# C3427-3.net
KiCad netlist of a schematic drawn in EAGLE
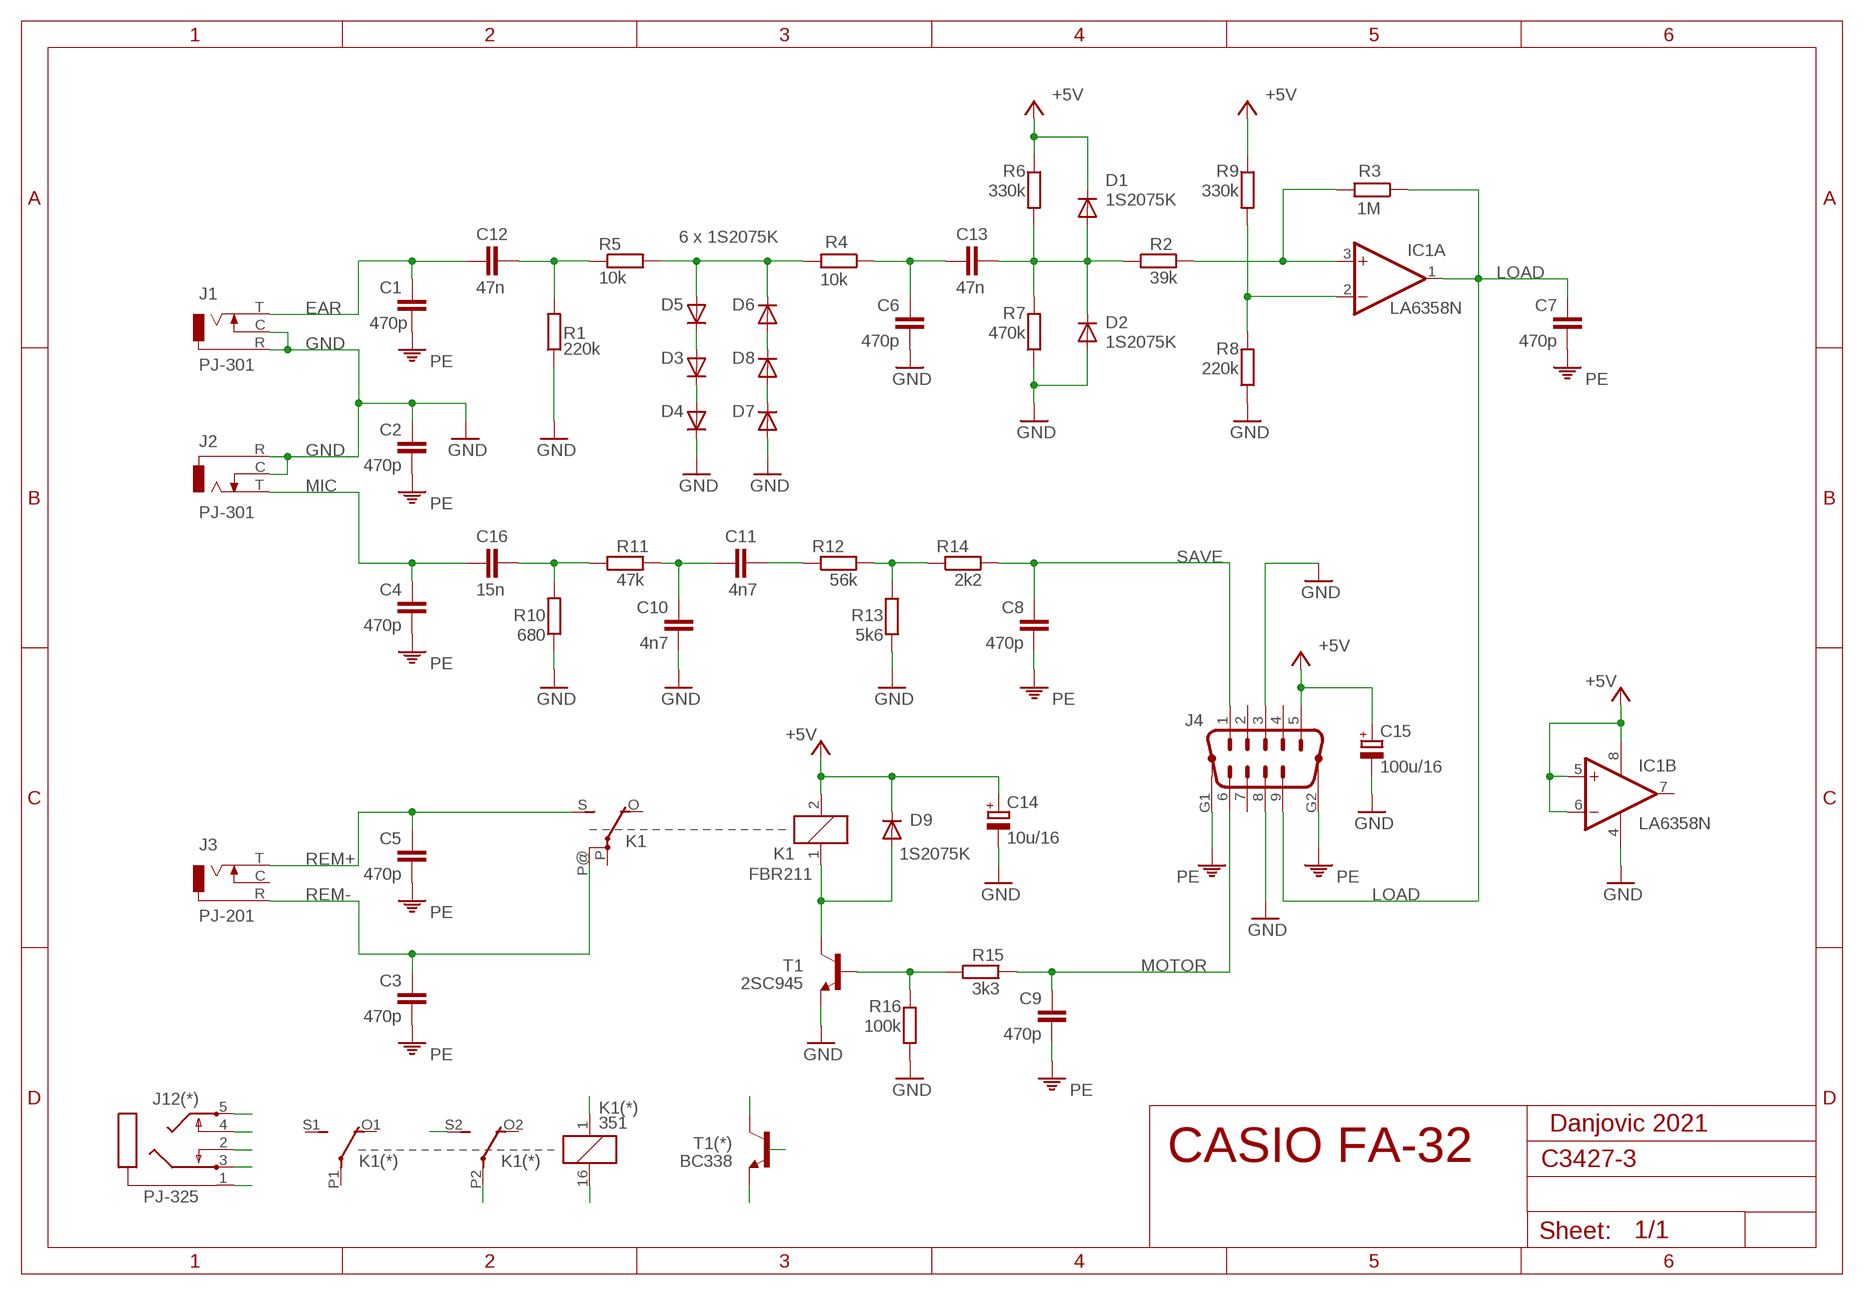
[diagram p0: schematic, sheet 1]

(export (version "E")
  (design (tool "Eeschema 10.0.6"))
  (components
    (comp (ref "C1")
      (value "470p")
      (footprint "eagle-import:C050-024X044")
      (libsource (lib "eagle-import") (part "C-EU050-024X044"))
    )
    (comp (ref "C2")
      (value "470p")
      (footprint "eagle-import:C050-024X044")
      (libsource (lib "eagle-import") (part "C-EU050-024X044"))
    )
    (comp (ref "C3")
      (value "470p")
      (footprint "eagle-import:C050-024X044")
      (libsource (lib "eagle-import") (part "C-EU050-024X044"))
    )
    (comp (ref "C4")
      (value "470p")
      (footprint "eagle-import:C050-024X044")
      (libsource (lib "eagle-import") (part "C-EU050-024X044"))
    )
    (comp (ref "C5")
      (value "470p")
      (footprint "eagle-import:C050-024X044")
      (libsource (lib "eagle-import") (part "C-EU050-024X044"))
    )
    (comp (ref "C6")
      (value "470p")
      (footprint "eagle-import:C050-024X044")
      (libsource (lib "eagle-import") (part "C-EU050-024X044"))
    )
    (comp (ref "C7")
      (value "470p")
      (footprint "eagle-import:C050-024X044")
      (libsource (lib "eagle-import") (part "C-EU050-024X044"))
    )
    (comp (ref "C8")
      (value "470p")
      (footprint "eagle-import:C050-024X044")
      (libsource (lib "eagle-import") (part "C-EU050-024X044"))
    )
    (comp (ref "C9")
      (value "470p")
      (footprint "eagle-import:C050-024X044")
      (libsource (lib "eagle-import") (part "C-EU050-024X044"))
    )
    (comp (ref "C10")
      (value "4n7")
      (footprint "eagle-import:C050-024X044")
      (libsource (lib "eagle-import") (part "C-EU050-024X044"))
    )
    (comp (ref "C11")
      (value "4n7")
      (footprint "eagle-import:C050-024X044")
      (libsource (lib "eagle-import") (part "C-EU050-024X044"))
    )
    (comp (ref "C12")
      (value "47n")
      (footprint "eagle-import:C050-045X075")
      (libsource (lib "eagle-import") (part "C-EU050-045X075"))
    )
    (comp (ref "C13")
      (value "47n")
      (footprint "eagle-import:C050-045X075")
      (libsource (lib "eagle-import") (part "C-EU050-045X075"))
    )
    (comp (ref "C14")
      (value "10u/16")
      (footprint "eagle-import:E2-4")
      (libsource (lib "eagle-import") (part "CPOL-EUE2-4"))
    )
    (comp (ref "C15")
      (value "100u/16")
      (footprint "eagle-import:E2,5-6")
      (libsource (lib "eagle-import") (part "CPOL-EUE2.5-6"))
    )
    (comp (ref "C16")
      (value "15n")
      (footprint "eagle-import:C050-024X044")
      (libsource (lib "eagle-import") (part "C-EU050-024X044"))
    )
    (comp (ref "D1")
      (value "1S2075K")
      (footprint "eagle-import:D-7.5")
      (libsource (lib "eagle-import") (part "DIODE-D-7.5"))
    )
    (comp (ref "D2")
      (value "1S2075K")
      (footprint "eagle-import:D-7.5")
      (libsource (lib "eagle-import") (part "DIODE-D-7.5"))
    )
    (comp (ref "D3")
      (value "1S2075K")
      (footprint "eagle-import:D-7.5")
      (libsource (lib "eagle-import") (part "DIODE-D-7.5"))
    )
    (comp (ref "D4")
      (value "1S2075K")
      (footprint "eagle-import:D-7.5")
      (libsource (lib "eagle-import") (part "DIODE-D-7.5"))
    )
    (comp (ref "D5")
      (value "1S2075K")
      (footprint "eagle-import:D-7.5")
      (libsource (lib "eagle-import") (part "DIODE-D-7.5"))
    )
    (comp (ref "D6")
      (value "1S2075K")
      (footprint "eagle-import:D-7.5")
      (libsource (lib "eagle-import") (part "DIODE-D-7.5"))
    )
    (comp (ref "D7")
      (value "1S2075K")
      (footprint "eagle-import:D-7.5")
      (libsource (lib "eagle-import") (part "DIODE-D-7.5"))
    )
    (comp (ref "D8")
      (value "1S2075K")
      (footprint "eagle-import:D-7.5")
      (libsource (lib "eagle-import") (part "DIODE-D-7.5"))
    )
    (comp (ref "D9")
      (value "1S2075K")
      (footprint "eagle-import:D-7.5")
      (libsource (lib "eagle-import") (part "DIODE-D-7.5"))
    )
    (comp (ref "IC1")
      (value "LA6358N")
      (footprint "eagle-import:DIL08")
      (libsource (lib "eagle-import") (part "LM358N"))
    )
    (comp (ref "J1")
      (value "PJ-301")
      (footprint "eagle-import:PJ301")
      (libsource (lib "eagle-import") (part "PJ-301"))
    )
    (comp (ref "J2")
      (value "PJ-301")
      (footprint "eagle-import:PJ301")
      (libsource (lib "eagle-import") (part "PJ-301"))
    )
    (comp (ref "J3")
      (value "PJ-201")
      (footprint "eagle-import:PJ201")
      (libsource (lib "eagle-import") (part "PJ-201"))
    )
    (comp (ref "J4")
      (value "M09HP")
      (footprint "eagle-import:M09HP")
      (libsource (lib "eagle-import") (part "M09HP"))
    )
    (comp (ref "J12(*)")
      (value "PJ-325")
      (footprint "eagle-import:PJ325")
      (libsource (lib "eagle-import") (part "PJ-325"))
    )
    (comp (ref "K1")
      (value "FBR211")
      (footprint "eagle-import:FRS1B")
      (libsource (lib "eagle-import") (part "FRS1B"))
    )
    (comp (ref "K1(*)")
      (value "351")
      (footprint "eagle-import:351")
      (libsource (lib "eagle-import") (part "351"))
    )
    (comp (ref "R1")
      (value "220k")
      (footprint "eagle-import:0204_7")
      (libsource (lib "eagle-import") (part "R-EU_0204/7"))
    )
    (comp (ref "R2")
      (value "39k")
      (footprint "eagle-import:0204_7")
      (libsource (lib "eagle-import") (part "R-EU_0204/7"))
    )
    (comp (ref "R3")
      (value "1M")
      (footprint "eagle-import:0204_7")
      (libsource (lib "eagle-import") (part "R-EU_0204/7"))
    )
    (comp (ref "R4")
      (value "10k")
      (footprint "eagle-import:0204_7")
      (libsource (lib "eagle-import") (part "R-EU_0204/7"))
    )
    (comp (ref "R5")
      (value "10k")
      (footprint "eagle-import:0204_7")
      (libsource (lib "eagle-import") (part "R-EU_0204/7"))
    )
    (comp (ref "R6")
      (value "330k")
      (footprint "eagle-import:0204_7")
      (libsource (lib "eagle-import") (part "R-EU_0204/7"))
    )
    (comp (ref "R7")
      (value "470k")
      (footprint "eagle-import:0204_7")
      (libsource (lib "eagle-import") (part "R-EU_0204/7"))
    )
    (comp (ref "R8")
      (value "220k")
      (footprint "eagle-import:0204_7")
      (libsource (lib "eagle-import") (part "R-EU_0204/7"))
    )
    (comp (ref "R9")
      (value "330k")
      (footprint "eagle-import:0204_7")
      (libsource (lib "eagle-import") (part "R-EU_0204/7"))
    )
    (comp (ref "R10")
      (value "680")
      (footprint "eagle-import:0204_7")
      (libsource (lib "eagle-import") (part "R-EU_0204/7"))
    )
    (comp (ref "R11")
      (value "47k")
      (footprint "eagle-import:0204_7")
      (libsource (lib "eagle-import") (part "R-EU_0204/7"))
    )
    (comp (ref "R12")
      (value "56k")
      (footprint "eagle-import:0204_7")
      (libsource (lib "eagle-import") (part "R-EU_0204/7"))
    )
    (comp (ref "R13")
      (value "5k6")
      (footprint "eagle-import:0204_7")
      (libsource (lib "eagle-import") (part "R-EU_0204/7"))
    )
    (comp (ref "R14")
      (value "2k2")
      (footprint "eagle-import:0204_7")
      (libsource (lib "eagle-import") (part "R-EU_0204/7"))
    )
    (comp (ref "R15")
      (value "3k3")
      (footprint "eagle-import:0204_7")
      (libsource (lib "eagle-import") (part "R-EU_0204/7"))
    )
    (comp (ref "R16")
      (value "100k")
      (footprint "eagle-import:0204_7")
      (libsource (lib "eagle-import") (part "R-EU_0204/7"))
    )
    (comp (ref "T1")
      (value "2SC945")
      (footprint "eagle-import:TO92-ECB")
      (libsource (lib "eagle-import") (part "2SC945"))
    )
    (comp (ref "T1(*)")
      (value "BC338")
      (footprint "eagle-import:TO92-EBC")
      (libsource (lib "eagle-import") (part "BC338"))
    )
  )
  (nets
    (net (code "1") (name "+5V") (class "Default")
      (node (ref "C14") (pin "+") (pinfunction "+_+") (pintype "passive"))
      (node (ref "C15") (pin "+") (pinfunction "+_+") (pintype "passive"))
      (node (ref "D1") (pin "C") (pinfunction "C_C") (pintype "passive"))
      (node (ref "D9") (pin "C") (pinfunction "C_C") (pintype "passive"))
      (node (ref "IC1") (pin "5") (pinfunction "+IN_5") (pintype "input"))
      (node (ref "IC1") (pin "6") (pinfunction "-IN_6") (pintype "input"))
      (node (ref "IC1") (pin "8") (pinfunction "V+_8") (pintype "power_in"))
      (node (ref "J4") (pin "5") (pinfunction "5_5") (pintype "passive"))
      (node (ref "K1") (pin "2") (pinfunction "2_2") (pintype "passive"))
      (node (ref "K1(*)") (pin "1") (pinfunction "1_1") (pintype "passive"))
      (node (ref "R6") (pin "1") (pinfunction "1_1") (pintype "passive"))
      (node (ref "R9") (pin "1") (pinfunction "1_1") (pintype "passive"))
    )
    (net (code "2") (name "/EAR") (class "Default")
      (node (ref "C1") (pin "2") (pinfunction "2_2") (pintype "passive"))
      (node (ref "C12") (pin "2") (pinfunction "2_2") (pintype "passive"))
      (node (ref "J1") (pin "T") (pinfunction "T_T") (pintype "passive"))
      (node (ref "J12(*)") (pin "5") (pinfunction "5_5") (pintype "passive"))
    )
    (net (code "3") (name "/LOAD") (class "Default")
      (node (ref "C7") (pin "2") (pinfunction "2_2") (pintype "passive"))
      (node (ref "IC1") (pin "1") (pinfunction "OUT_1") (pintype "output"))
      (node (ref "J4") (pin "9") (pinfunction "9_9") (pintype "passive"))
      (node (ref "R3") (pin "1") (pinfunction "1_1") (pintype "passive"))
    )
    (net (code "4") (name "/MIC") (class "Default")
      (node (ref "C16") (pin "2") (pinfunction "2_2") (pintype "passive"))
      (node (ref "C4") (pin "2") (pinfunction "2_2") (pintype "passive"))
      (node (ref "J12(*)") (pin "3") (pinfunction "3_3") (pintype "passive"))
      (node (ref "J2") (pin "T") (pinfunction "T_T") (pintype "passive"))
    )
    (net (code "5") (name "/MOTOR") (class "Default")
      (node (ref "C9") (pin "2") (pinfunction "2_2") (pintype "passive"))
      (node (ref "J4") (pin "6") (pinfunction "6_6") (pintype "passive"))
      (node (ref "R15") (pin "2") (pinfunction "2_2") (pintype "passive"))
    )
    (net (code "6") (name "/N$9") (class "Default")
      (node (ref "D9") (pin "A") (pinfunction "A_A") (pintype "passive"))
      (node (ref "K1") (pin "1") (pinfunction "1_1") (pintype "passive"))
      (node (ref "K1(*)") (pin "16") (pinfunction "2_16") (pintype "passive"))
      (node (ref "T1") (pin "C") (pinfunction "C_C") (pintype "passive"))
      (node (ref "T1(*)") (pin "C") (pinfunction "C_C") (pintype "passive"))
    )
    (net (code "7") (name "/N$10") (class "Default")
      (node (ref "R15") (pin "1") (pinfunction "1_1") (pintype "passive"))
      (node (ref "R16") (pin "1") (pinfunction "1_1") (pintype "passive"))
      (node (ref "T1") (pin "B") (pinfunction "B_B") (pintype "passive"))
      (node (ref "T1(*)") (pin "B") (pinfunction "B_B") (pintype "passive"))
    )
    (net (code "8") (name "/REM+") (class "Default")
      (node (ref "C5") (pin "2") (pinfunction "2_2") (pintype "passive"))
      (node (ref "J3") (pin "T") (pinfunction "T_T") (pintype "passive"))
      (node (ref "K1") (pin "S") (pinfunction "S_S") (pintype "passive"))
      (node (ref "K1(*)") (pin "P2") (pinfunction "P_P2") (pintype "passive"))
    )
    (net (code "9") (name "/REM-") (class "Default")
      (node (ref "C3") (pin "2") (pinfunction "2_2") (pintype "passive"))
      (node (ref "J3") (pin "R") (pinfunction "R_R") (pintype "passive"))
      (node (ref "K1") (pin "P@") (pinfunction "P_P@") (pintype "passive"))
      (node (ref "K1(*)") (pin "S2") (pinfunction "S_S2") (pintype "passive"))
    )
    (net (code "10") (name "/SAVE") (class "Default")
      (node (ref "C8") (pin "2") (pinfunction "2_2") (pintype "passive"))
      (node (ref "J4") (pin "1") (pinfunction "1_1") (pintype "passive"))
      (node (ref "R14") (pin "2") (pinfunction "2_2") (pintype "passive"))
    )
    (net (code "11") (name "GND") (class "Default")
      (node (ref "C10") (pin "1") (pinfunction "1_1") (pintype "passive"))
      (node (ref "C14") (pin "-") (pinfunction "-_-") (pintype "passive"))
      (node (ref "C15") (pin "-") (pinfunction "-_-") (pintype "passive"))
      (node (ref "C2") (pin "2") (pinfunction "2_2") (pintype "passive"))
      (node (ref "C6") (pin "1") (pinfunction "1_1") (pintype "passive"))
      (node (ref "D2") (pin "A") (pinfunction "A_A") (pintype "passive"))
      (node (ref "D4") (pin "C") (pinfunction "C_C") (pintype "passive"))
      (node (ref "D7") (pin "A") (pinfunction "A_A") (pintype "passive"))
      (node (ref "IC1") (pin "4") (pinfunction "V-_4") (pintype "power_in"))
      (node (ref "J1") (pin "C") (pinfunction "C_C") (pintype "passive"))
      (node (ref "J1") (pin "R") (pinfunction "R_R") (pintype "passive"))
      (node (ref "J12(*)") (pin "1") (pinfunction "1_1") (pintype "passive"))
      (node (ref "J12(*)") (pin "2") (pinfunction "2_2") (pintype "passive"))
      (node (ref "J12(*)") (pin "4") (pinfunction "4_4") (pintype "passive"))
      (node (ref "J2") (pin "C") (pinfunction "C_C") (pintype "passive"))
      (node (ref "J2") (pin "R") (pinfunction "R_R") (pintype "passive"))
      (node (ref "J4") (pin "3") (pinfunction "3_3") (pintype "passive"))
      (node (ref "J4") (pin "8") (pinfunction "8_8") (pintype "passive"))
      (node (ref "R1") (pin "1") (pinfunction "1_1") (pintype "passive"))
      (node (ref "R10") (pin "1") (pinfunction "1_1") (pintype "passive"))
      (node (ref "R13") (pin "2") (pinfunction "2_2") (pintype "passive"))
      (node (ref "R16") (pin "2") (pinfunction "2_2") (pintype "passive"))
      (node (ref "R7") (pin "1") (pinfunction "1_1") (pintype "passive"))
      (node (ref "R8") (pin "1") (pinfunction "1_1") (pintype "passive"))
      (node (ref "T1") (pin "E") (pinfunction "E_E") (pintype "passive"))
      (node (ref "T1(*)") (pin "E") (pinfunction "E_E") (pintype "passive"))
    )
    (net (code "12") (name "Net-(C10-Pad2)") (class "Default")
      (node (ref "C10") (pin "2") (pinfunction "2_2") (pintype "passive"))
      (node (ref "C11") (pin "1") (pinfunction "1_1") (pintype "passive"))
      (node (ref "R11") (pin "2") (pinfunction "2_2") (pintype "passive"))
    )
    (net (code "13") (name "Net-(C11-Pad2)") (class "Default")
      (node (ref "C11") (pin "2") (pinfunction "2_2") (pintype "passive"))
      (node (ref "R12") (pin "1") (pinfunction "1_1") (pintype "passive"))
    )
    (net (code "14") (name "Net-(C12-Pad1)") (class "Default")
      (node (ref "C12") (pin "1") (pinfunction "1_1") (pintype "passive"))
      (node (ref "R1") (pin "2") (pinfunction "2_2") (pintype "passive"))
      (node (ref "R5") (pin "1") (pinfunction "1_1") (pintype "passive"))
    )
    (net (code "15") (name "Net-(C13-Pad1)") (class "Default")
      (node (ref "C13") (pin "1") (pinfunction "1_1") (pintype "passive"))
      (node (ref "D1") (pin "A") (pinfunction "A_A") (pintype "passive"))
      (node (ref "D2") (pin "C") (pinfunction "C_C") (pintype "passive"))
      (node (ref "R2") (pin "1") (pinfunction "1_1") (pintype "passive"))
      (node (ref "R6") (pin "2") (pinfunction "2_2") (pintype "passive"))
      (node (ref "R7") (pin "2") (pinfunction "2_2") (pintype "passive"))
    )
    (net (code "16") (name "Net-(C13-Pad2)") (class "Default")
      (node (ref "C13") (pin "2") (pinfunction "2_2") (pintype "passive"))
      (node (ref "C6") (pin "2") (pinfunction "2_2") (pintype "passive"))
      (node (ref "R4") (pin "1") (pinfunction "1_1") (pintype "passive"))
    )
    (net (code "17") (name "Net-(C16-Pad1)") (class "Default")
      (node (ref "C16") (pin "1") (pinfunction "1_1") (pintype "passive"))
      (node (ref "R10") (pin "2") (pinfunction "2_2") (pintype "passive"))
      (node (ref "R11") (pin "1") (pinfunction "1_1") (pintype "passive"))
    )
    (net (code "18") (name "Net-(D3-PadA)") (class "Default")
      (node (ref "D3") (pin "A") (pinfunction "A_A") (pintype "passive"))
      (node (ref "D5") (pin "C") (pinfunction "C_C") (pintype "passive"))
    )
    (net (code "19") (name "Net-(D3-PadC)") (class "Default")
      (node (ref "D3") (pin "C") (pinfunction "C_C") (pintype "passive"))
      (node (ref "D4") (pin "A") (pinfunction "A_A") (pintype "passive"))
    )
    (net (code "20") (name "Net-(D5-PadA)") (class "Default")
      (node (ref "D5") (pin "A") (pinfunction "A_A") (pintype "passive"))
      (node (ref "D6") (pin "C") (pinfunction "C_C") (pintype "passive"))
      (node (ref "R4") (pin "2") (pinfunction "2_2") (pintype "passive"))
      (node (ref "R5") (pin "2") (pinfunction "2_2") (pintype "passive"))
    )
    (net (code "21") (name "Net-(D6-PadA)") (class "Default")
      (node (ref "D6") (pin "A") (pinfunction "A_A") (pintype "passive"))
      (node (ref "D8") (pin "C") (pinfunction "C_C") (pintype "passive"))
    )
    (net (code "22") (name "Net-(D7-PadC)") (class "Default")
      (node (ref "D7") (pin "C") (pinfunction "C_C") (pintype "passive"))
      (node (ref "D8") (pin "A") (pinfunction "A_A") (pintype "passive"))
    )
    (net (code "23") (name "Net-(IC1A-+IN)") (class "Default")
      (node (ref "IC1") (pin "3") (pinfunction "+IN_3") (pintype "input"))
      (node (ref "R2") (pin "2") (pinfunction "2_2") (pintype "passive"))
      (node (ref "R3") (pin "2") (pinfunction "2_2") (pintype "passive"))
    )
    (net (code "24") (name "Net-(IC1A--IN)") (class "Default")
      (node (ref "IC1") (pin "2") (pinfunction "-IN_2") (pintype "input"))
      (node (ref "R8") (pin "2") (pinfunction "2_2") (pintype "passive"))
      (node (ref "R9") (pin "2") (pinfunction "2_2") (pintype "passive"))
    )
    (net (code "25") (name "Net-(R12-Pad2)") (class "Default")
      (node (ref "R12") (pin "2") (pinfunction "2_2") (pintype "passive"))
      (node (ref "R13") (pin "1") (pinfunction "1_1") (pintype "passive"))
      (node (ref "R14") (pin "1") (pinfunction "1_1") (pintype "passive"))
    )
    (net (code "26") (name "PE") (class "Default")
      (node (ref "C1") (pin "1") (pinfunction "1_1") (pintype "passive"))
      (node (ref "C2") (pin "1") (pinfunction "1_1") (pintype "passive"))
      (node (ref "C3") (pin "1") (pinfunction "1_1") (pintype "passive"))
      (node (ref "C4") (pin "1") (pinfunction "1_1") (pintype "passive"))
      (node (ref "C5") (pin "1") (pinfunction "1_1") (pintype "passive"))
      (node (ref "C7") (pin "1") (pinfunction "1_1") (pintype "passive"))
      (node (ref "C8") (pin "1") (pinfunction "1_1") (pintype "passive"))
      (node (ref "C9") (pin "1") (pinfunction "1_1") (pintype "passive"))
      (node (ref "J4") (pin "G1") (pinfunction "G1_G1") (pintype "passive"))
      (node (ref "J4") (pin "G2") (pinfunction "G2_G2") (pintype "passive"))
    )
    (net (code "27") (name "unconnected-(IC1B-OUT-Pad7)") (class "Default")
      (node (ref "IC1") (pin "7") (pinfunction "OUT_7") (pintype "output"))
    )
    (net (code "28") (name "unconnected-(J3-PadC)") (class "Default")
      (node (ref "J3") (pin "C") (pinfunction "C_C") (pintype "passive"))
    )
    (net (code "29") (name "unconnected-(J4-Pad2)") (class "Default")
      (node (ref "J4") (pin "2") (pinfunction "2_2") (pintype "passive"))
    )
    (net (code "30") (name "unconnected-(J4-Pad4)") (class "Default")
      (node (ref "J4") (pin "4") (pinfunction "4_4") (pintype "passive"))
    )
    (net (code "31") (name "unconnected-(J4-Pad7)") (class "Default")
      (node (ref "J4") (pin "7") (pinfunction "7_7") (pintype "passive"))
    )
    (net (code "32") (name "unconnected-(K1(*)B-O-PadO1)") (class "Default")
      (node (ref "K1(*)") (pin "O1") (pinfunction "O_O1") (pintype "passive"))
    )
    (net (code "33") (name "unconnected-(K1(*)B-P-PadP1)") (class "Default")
      (node (ref "K1(*)") (pin "P1") (pinfunction "P_P1") (pintype "passive"))
    )
    (net (code "34") (name "unconnected-(K1(*)B-S-PadS1)") (class "Default")
      (node (ref "K1(*)") (pin "S1") (pinfunction "S_S1") (pintype "passive"))
    )
    (net (code "35") (name "unconnected-(K1(*)C-O-PadO2)") (class "Default")
      (node (ref "K1(*)") (pin "O2") (pinfunction "O_O2") (pintype "passive"))
    )
    (net (code "36") (name "unconnected-(K1-PadO)") (class "Default")
      (node (ref "K1") (pin "O") (pinfunction "O_O") (pintype "passive"))
    )
    (net (code "37") (name "unconnected-(K1-PadP)") (class "Default")
      (node (ref "K1") (pin "P") (pinfunction "P_P") (pintype "passive"))
    )
  )
)
